# K_pfh_rerverst_rker_PSU_Rev_1_1.net
KiCad netlist of a schematic drawn in EAGLE
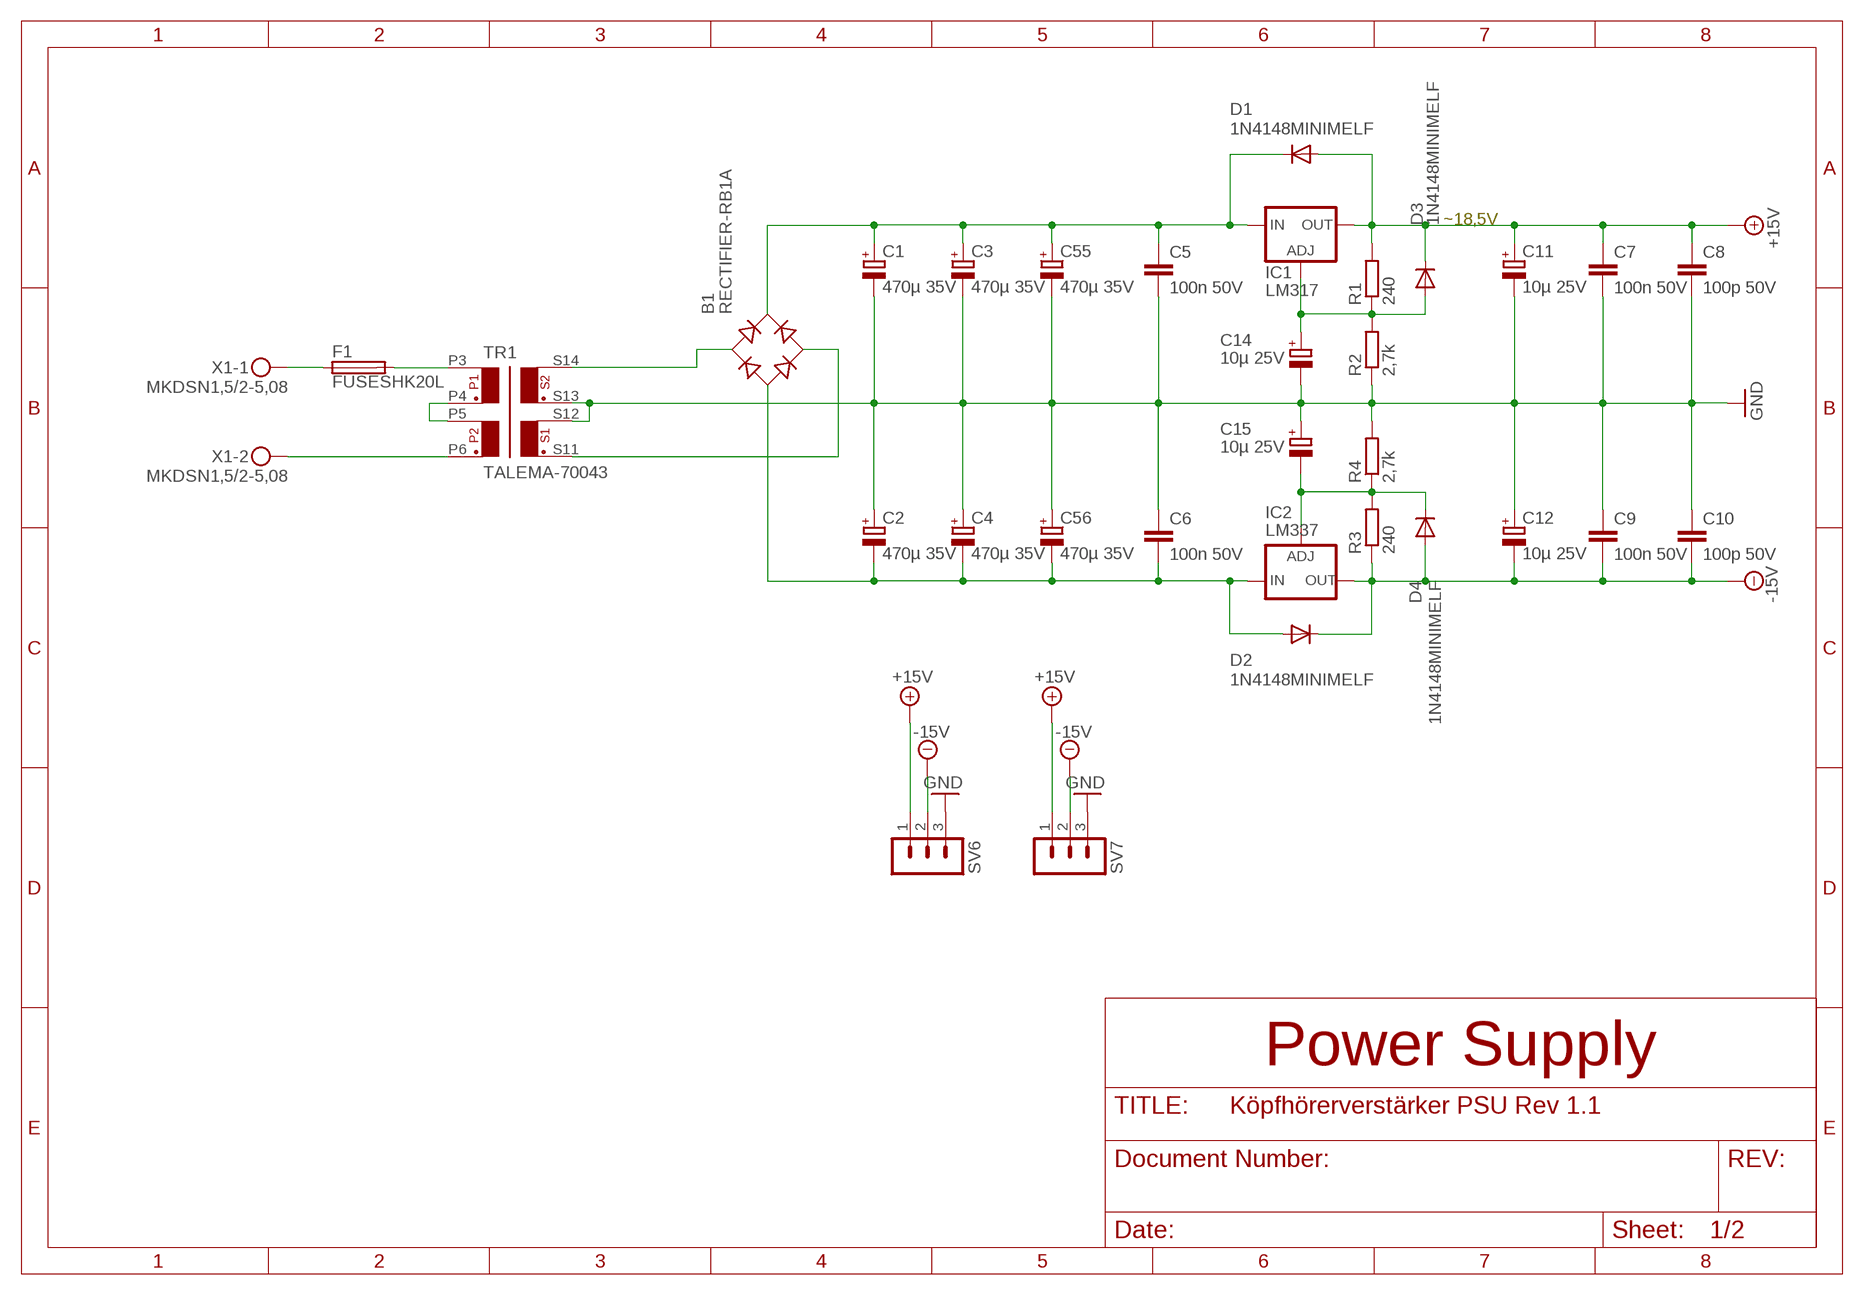
[diagram p0: schematic, sheet 1]
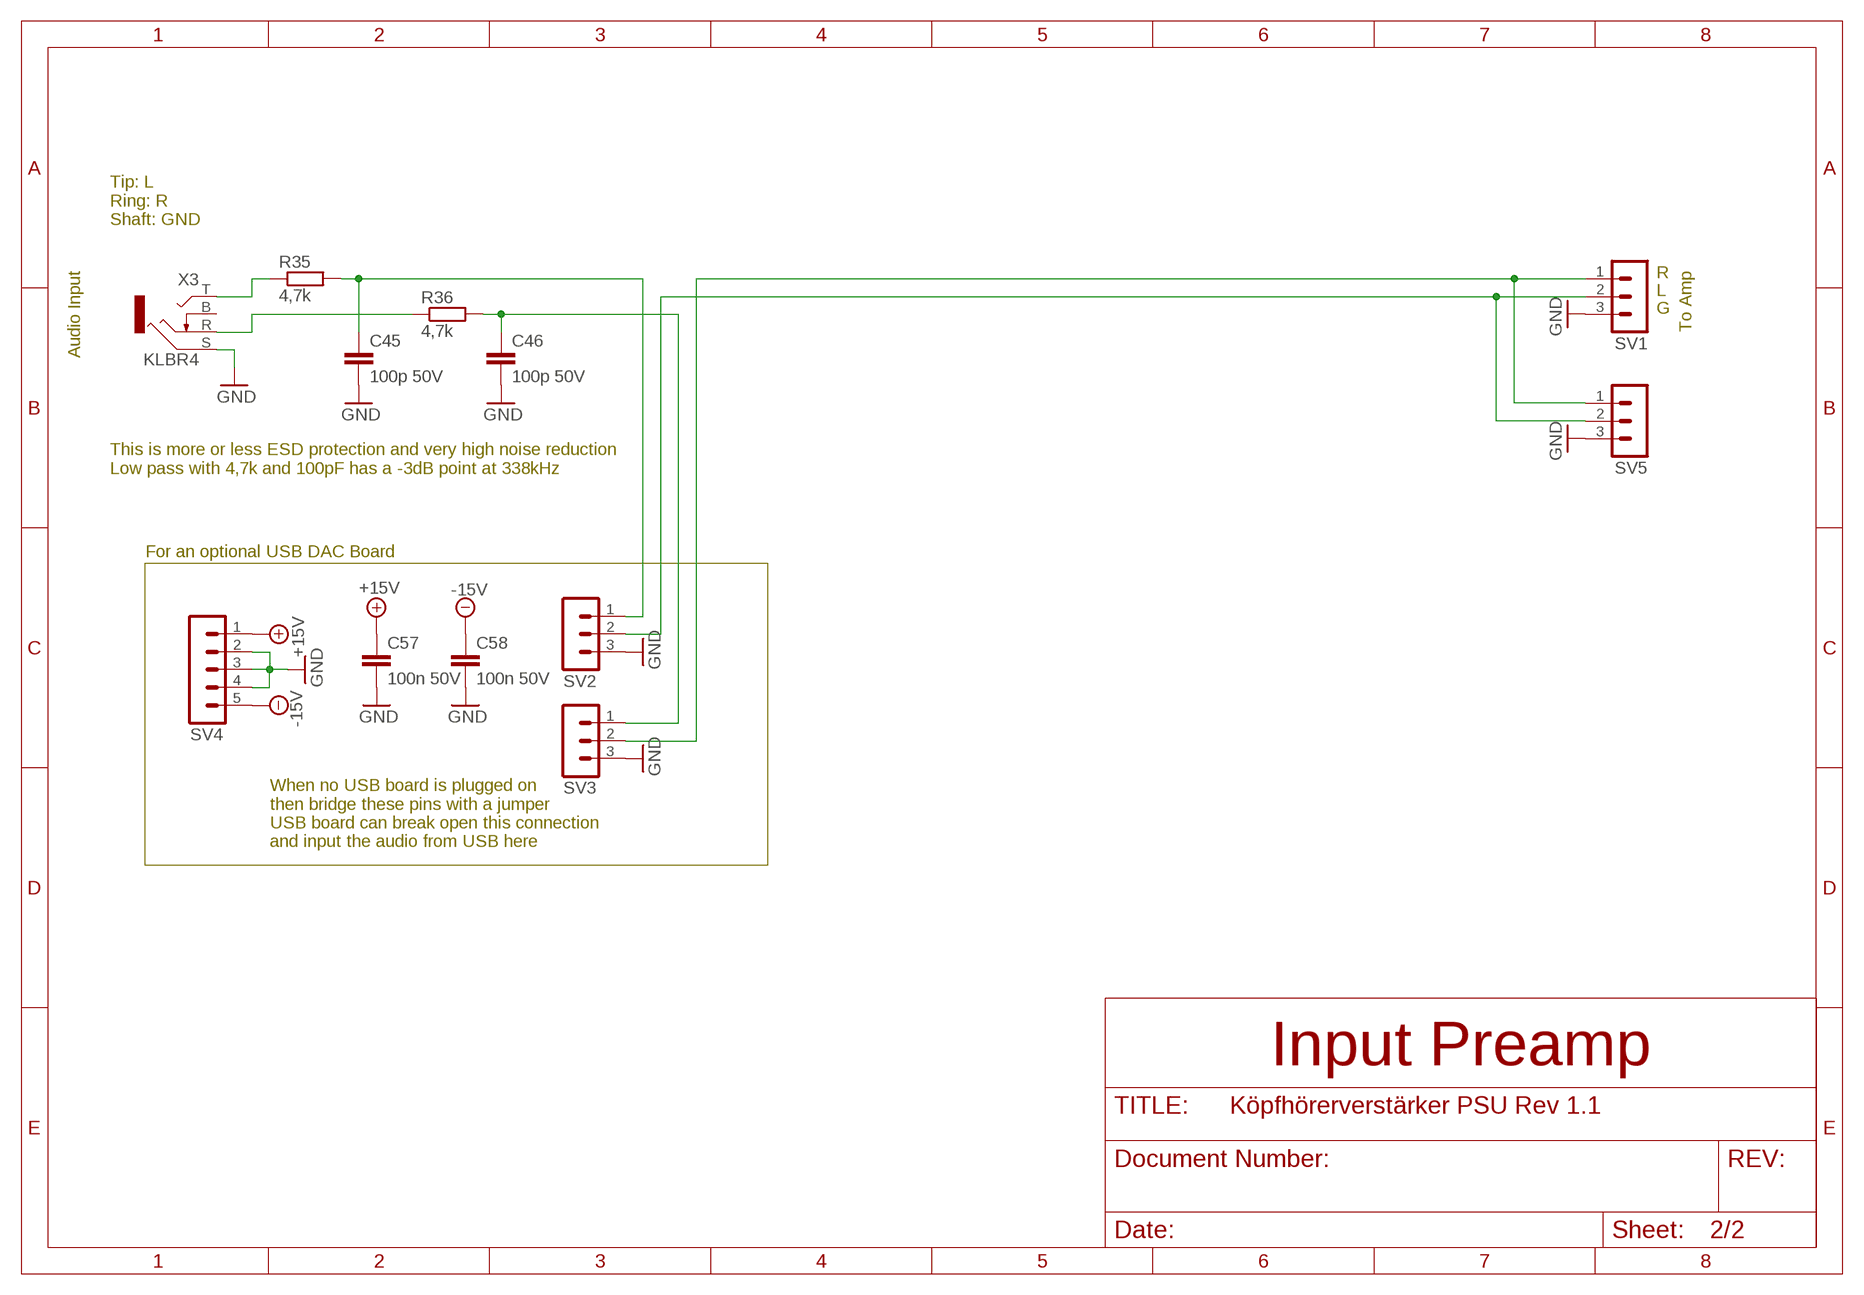
[diagram p1: schematic, sheet 2]

(export (version "E")
  (design (tool "Eeschema 10.0.6"))
  (components
    (comp (ref "B1")
      (value "RECTIFIER-RB1A")
      (footprint "eagle-import:RB1A")
      (libsource (lib "eagle-import") (part "RECTIFIER-RB1A"))
    )
    (comp (ref "C1")
      (value "470µ 35V")
      (footprint "eagle-import:E5-10,5")
      (libsource (lib "eagle-import") (part "CPOL-EUE5-10.5"))
    )
    (comp (ref "C2")
      (value "470µ 35V")
      (footprint "eagle-import:E5-10,5")
      (libsource (lib "eagle-import") (part "CPOL-EUE5-10.5"))
    )
    (comp (ref "C3")
      (value "470µ 35V")
      (footprint "eagle-import:E5-10,5")
      (libsource (lib "eagle-import") (part "CPOL-EUE5-10.5"))
    )
    (comp (ref "C4")
      (value "470µ 35V")
      (footprint "eagle-import:E5-10,5")
      (libsource (lib "eagle-import") (part "CPOL-EUE5-10.5"))
    )
    (comp (ref "C5")
      (value "100n 50V")
      (footprint "eagle-import:C0805")
      (libsource (lib "eagle-import") (part "C-EUC0805"))
    )
    (comp (ref "C6")
      (value "100n 50V")
      (footprint "eagle-import:C0805")
      (libsource (lib "eagle-import") (part "C-EUC0805"))
    )
    (comp (ref "C7")
      (value "100n 50V")
      (footprint "eagle-import:C0805")
      (libsource (lib "eagle-import") (part "C-EUC0805"))
    )
    (comp (ref "C8")
      (value "100p 50V")
      (footprint "eagle-import:C0805")
      (libsource (lib "eagle-import") (part "C-EUC0805"))
    )
    (comp (ref "C9")
      (value "100n 50V")
      (footprint "eagle-import:C0805")
      (libsource (lib "eagle-import") (part "C-EUC0805"))
    )
    (comp (ref "C10")
      (value "100p 50V")
      (footprint "eagle-import:C0805")
      (libsource (lib "eagle-import") (part "C-EUC0805"))
    )
    (comp (ref "C11")
      (value "10µ 25V")
      (footprint "eagle-import:E2,5-5")
      (libsource (lib "eagle-import") (part "CPOL-EUE2.5-5"))
    )
    (comp (ref "C12")
      (value "10µ 25V")
      (footprint "eagle-import:E2,5-5")
      (libsource (lib "eagle-import") (part "CPOL-EUE2.5-5"))
    )
    (comp (ref "C14")
      (value "10µ 25V")
      (footprint "eagle-import:E2,5-5")
      (libsource (lib "eagle-import") (part "CPOL-EUE2.5-5"))
    )
    (comp (ref "C15")
      (value "10µ 25V")
      (footprint "eagle-import:E2,5-5")
      (libsource (lib "eagle-import") (part "CPOL-EUE2.5-5"))
    )
    (comp (ref "C55")
      (value "470µ 35V")
      (footprint "eagle-import:E5-10,5")
      (libsource (lib "eagle-import") (part "CPOL-EUE5-10.5"))
    )
    (comp (ref "C56")
      (value "470µ 35V")
      (footprint "eagle-import:E5-10,5")
      (libsource (lib "eagle-import") (part "CPOL-EUE5-10.5"))
    )
    (comp (ref "D1")
      (value "1N4148MINIMELF")
      (footprint "eagle-import:MINIMELF")
      (libsource (lib "eagle-import") (part "1N4148MINIMELF"))
    )
    (comp (ref "D2")
      (value "1N4148MINIMELF")
      (footprint "eagle-import:MINIMELF")
      (libsource (lib "eagle-import") (part "1N4148MINIMELF"))
    )
    (comp (ref "D3")
      (value "1N4148MINIMELF")
      (footprint "eagle-import:MINIMELF")
      (libsource (lib "eagle-import") (part "1N4148MINIMELF"))
    )
    (comp (ref "D4")
      (value "1N4148MINIMELF")
      (footprint "eagle-import:MINIMELF")
      (libsource (lib "eagle-import") (part "1N4148MINIMELF"))
    )
    (comp (ref "F1")
      (value "FUSESHK20L")
      (footprint "eagle-import:SHK20L")
      (libsource (lib "eagle-import") (part "FUSESHK20L"))
    )
    (comp (ref "IC1")
      (value "LM317")
      (footprint "eagle-import:317TL")
      (libsource (lib "eagle-import") (part "LM317TL"))
    )
    (comp (ref "IC2")
      (value "LM337")
      (footprint "eagle-import:337TL")
      (libsource (lib "eagle-import") (part "LM337TL"))
    )
    (comp (ref "R1")
      (value "240")
      (footprint "eagle-import:R0805")
      (libsource (lib "eagle-import") (part "R-EU_R0805"))
    )
    (comp (ref "R2")
      (value "2,7k")
      (footprint "eagle-import:R0805")
      (libsource (lib "eagle-import") (part "R-EU_R0805"))
    )
    (comp (ref "R3")
      (value "240")
      (footprint "eagle-import:R0805")
      (libsource (lib "eagle-import") (part "R-EU_R0805"))
    )
    (comp (ref "R4")
      (value "2,7k")
      (footprint "eagle-import:R0805")
      (libsource (lib "eagle-import") (part "R-EU_R0805"))
    )
    (comp (ref "SV6")
      (value "MA03-1")
      (footprint "eagle-import:MA03-1")
      (libsource (lib "eagle-import") (part "MA03-1"))
    )
    (comp (ref "SV7")
      (value "MA03-1")
      (footprint "eagle-import:MA03-1")
      (libsource (lib "eagle-import") (part "MA03-1"))
    )
    (comp (ref "TR1")
      (value "TALEMA-70043")
      (footprint "eagle-import:TALEMA-70043")
      (libsource (lib "eagle-import") (part "TALEMA-70043"))
    )
    (comp (ref "X1")
      (value "MKDSN1,5/2-5,08")
      (footprint "eagle-import:MKDSN1,5_2-5,08")
      (fields (field (name "MPN") "MKDSN 1,5/2-5.08"))
      (libsource (lib "eagle-import") (part "MKDSN1,5/2-5,08"))
    )
    (comp (ref "C45")
      (value "100p 50V")
      (footprint "eagle-import:C050-025X075")
      (libsource (lib "eagle-import") (part "C-EU050-025X075"))
    )
    (comp (ref "C46")
      (value "100p 50V")
      (footprint "eagle-import:C050-025X075")
      (libsource (lib "eagle-import") (part "C-EU050-025X075"))
    )
    (comp (ref "C57")
      (value "100n 50V")
      (footprint "eagle-import:C0805")
      (libsource (lib "eagle-import") (part "C-EUC0805"))
    )
    (comp (ref "C58")
      (value "100n 50V")
      (footprint "eagle-import:C0805")
      (libsource (lib "eagle-import") (part "C-EUC0805"))
    )
    (comp (ref "R35")
      (value "4,7k")
      (footprint "eagle-import:R0805")
      (libsource (lib "eagle-import") (part "R-EU_R0805"))
    )
    (comp (ref "R36")
      (value "4,7k")
      (footprint "eagle-import:R0805")
      (libsource (lib "eagle-import") (part "R-EU_R0805"))
    )
    (comp (ref "SV1")
      (value "MA03-1")
      (footprint "eagle-import:MA03-1")
      (libsource (lib "eagle-import") (part "MA03-1"))
    )
    (comp (ref "SV2")
      (value "MA03-1")
      (footprint "eagle-import:MA03-1")
      (libsource (lib "eagle-import") (part "MA03-1"))
    )
    (comp (ref "SV3")
      (value "MA03-1")
      (footprint "eagle-import:MA03-1")
      (libsource (lib "eagle-import") (part "MA03-1"))
    )
    (comp (ref "SV4")
      (value "MA05-1")
      (footprint "eagle-import:MA05-1")
      (libsource (lib "eagle-import") (part "MA05-1"))
    )
    (comp (ref "SV5")
      (value "MA03-1")
      (footprint "eagle-import:MA03-1")
      (libsource (lib "eagle-import") (part "MA03-1"))
    )
    (comp (ref "X3")
      (value "KLBR4")
      (footprint "eagle-import:KLBR4")
      (fields (field (name "MPN") "KLBR 4"))
      (libsource (lib "eagle-import") (part "KLBR4"))
    )
  )
  (nets
    (net (code "1") (name "+15V") (class "Default")
      (node (ref "C11") (pin "+") (pinfunction "+_+") (pintype "passive"))
      (node (ref "C57") (pin "1") (pinfunction "1_1") (pintype "passive"))
      (node (ref "C7") (pin "1") (pinfunction "1_1") (pintype "passive"))
      (node (ref "C8") (pin "1") (pinfunction "1_1") (pintype "passive"))
      (node (ref "D1") (pin "A") (pinfunction "A_A") (pintype "passive"))
      (node (ref "D3") (pin "C") (pinfunction "C_C") (pintype "passive"))
      (node (ref "IC1") (pin "2") (pinfunction "OUT_2") (pintype "passive"))
      (node (ref "R1") (pin "2") (pinfunction "2_2") (pintype "passive"))
      (node (ref "SV4") (pin "1") (pinfunction "1_1") (pintype "passive"))
      (node (ref "SV6") (pin "1") (pinfunction "1_1") (pintype "passive"))
      (node (ref "SV7") (pin "1") (pinfunction "1_1") (pintype "passive"))
    )
    (net (code "2") (name "-15V") (class "Default")
      (node (ref "C10") (pin "2") (pinfunction "2_2") (pintype "passive"))
      (node (ref "C12") (pin "-") (pinfunction "-_-") (pintype "passive"))
      (node (ref "C58") (pin "1") (pinfunction "1_1") (pintype "passive"))
      (node (ref "C9") (pin "2") (pinfunction "2_2") (pintype "passive"))
      (node (ref "D2") (pin "C") (pinfunction "C_C") (pintype "passive"))
      (node (ref "D4") (pin "A") (pinfunction "A_A") (pintype "passive"))
      (node (ref "IC2") (pin "3") (pinfunction "OUT_3") (pintype "passive"))
      (node (ref "R3") (pin "1") (pinfunction "1_1") (pintype "passive"))
      (node (ref "SV4") (pin "5") (pinfunction "5_5") (pintype "passive"))
      (node (ref "SV6") (pin "2") (pinfunction "2_2") (pintype "passive"))
      (node (ref "SV7") (pin "2") (pinfunction "2_2") (pintype "passive"))
    )
    (net (code "3") (name "GND") (class "Default")
      (node (ref "C1") (pin "-") (pinfunction "-_-") (pintype "passive"))
      (node (ref "C10") (pin "1") (pinfunction "1_1") (pintype "passive"))
      (node (ref "C11") (pin "-") (pinfunction "-_-") (pintype "passive"))
      (node (ref "C12") (pin "+") (pinfunction "+_+") (pintype "passive"))
      (node (ref "C14") (pin "-") (pinfunction "-_-") (pintype "passive"))
      (node (ref "C15") (pin "+") (pinfunction "+_+") (pintype "passive"))
      (node (ref "C2") (pin "+") (pinfunction "+_+") (pintype "passive"))
      (node (ref "C3") (pin "-") (pinfunction "-_-") (pintype "passive"))
      (node (ref "C4") (pin "+") (pinfunction "+_+") (pintype "passive"))
      (node (ref "C45") (pin "2") (pinfunction "2_2") (pintype "passive"))
      (node (ref "C46") (pin "2") (pinfunction "2_2") (pintype "passive"))
      (node (ref "C5") (pin "2") (pinfunction "2_2") (pintype "passive"))
      (node (ref "C55") (pin "-") (pinfunction "-_-") (pintype "passive"))
      (node (ref "C56") (pin "+") (pinfunction "+_+") (pintype "passive"))
      (node (ref "C57") (pin "2") (pinfunction "2_2") (pintype "passive"))
      (node (ref "C58") (pin "2") (pinfunction "2_2") (pintype "passive"))
      (node (ref "C6") (pin "1") (pinfunction "1_1") (pintype "passive"))
      (node (ref "C7") (pin "2") (pinfunction "2_2") (pintype "passive"))
      (node (ref "C8") (pin "2") (pinfunction "2_2") (pintype "passive"))
      (node (ref "C9") (pin "1") (pinfunction "1_1") (pintype "passive"))
      (node (ref "R2") (pin "1") (pinfunction "1_1") (pintype "passive"))
      (node (ref "R4") (pin "2") (pinfunction "2_2") (pintype "passive"))
      (node (ref "SV1") (pin "3") (pinfunction "3_3") (pintype "passive"))
      (node (ref "SV2") (pin "3") (pinfunction "3_3") (pintype "passive"))
      (node (ref "SV3") (pin "3") (pinfunction "3_3") (pintype "passive"))
      (node (ref "SV4") (pin "2") (pinfunction "2_2") (pintype "passive"))
      (node (ref "SV4") (pin "3") (pinfunction "3_3") (pintype "passive"))
      (node (ref "SV4") (pin "4") (pinfunction "4_4") (pintype "passive"))
      (node (ref "SV5") (pin "3") (pinfunction "3_3") (pintype "passive"))
      (node (ref "SV6") (pin "3") (pinfunction "3_3") (pintype "passive"))
      (node (ref "SV7") (pin "3") (pinfunction "3_3") (pintype "passive"))
      (node (ref "TR1") (pin "S12") (pinfunction "6_S12") (pintype "passive"))
      (node (ref "TR1") (pin "S13") (pinfunction "7_S13") (pintype "passive"))
      (node (ref "X3") (pin "S") (pinfunction "S_S") (pintype "passive"))
    )
    (net (code "4") (name "Net-(C45-Pad1)") (class "Default")
      (node (ref "C45") (pin "1") (pinfunction "1_1") (pintype "passive"))
      (node (ref "R35") (pin "2") (pinfunction "2_2") (pintype "passive"))
      (node (ref "SV2") (pin "1") (pinfunction "1_1") (pintype "passive"))
    )
    (net (code "5") (name "Net-(C46-Pad1)") (class "Default")
      (node (ref "C46") (pin "1") (pinfunction "1_1") (pintype "passive"))
      (node (ref "R36") (pin "2") (pinfunction "2_2") (pintype "passive"))
      (node (ref "SV3") (pin "1") (pinfunction "1_1") (pintype "passive"))
    )
    (net (code "6") (name "Net-(F1-1)") (class "Default")
      (node (ref "F1") (pin "1A") (pinfunction "1_1A") (pintype "passive"))
      (node (ref "X1") (pin "1") (pinfunction "KL_1") (pintype "passive"))
    )
    (net (code "7") (name "Net-(F1-2)") (class "Default")
      (node (ref "F1") (pin "2A") (pinfunction "2_2A") (pintype "passive"))
      (node (ref "TR1") (pin "P3") (pinfunction "1_P3") (pintype "passive"))
    )
    (net (code "8") (name "Net-(IC1-ADJ)") (class "Default")
      (node (ref "C14") (pin "+") (pinfunction "+_+") (pintype "passive"))
      (node (ref "D3") (pin "A") (pinfunction "A_A") (pintype "passive"))
      (node (ref "IC1") (pin "1") (pinfunction "ADJ_1") (pintype "input"))
      (node (ref "R1") (pin "1") (pinfunction "1_1") (pintype "passive"))
      (node (ref "R2") (pin "2") (pinfunction "2_2") (pintype "passive"))
    )
    (net (code "9") (name "Net-(IC1-IN)") (class "Default")
      (node (ref "B1") (pin "+") (pinfunction "+_+") (pintype "passive"))
      (node (ref "C1") (pin "+") (pinfunction "+_+") (pintype "passive"))
      (node (ref "C3") (pin "+") (pinfunction "+_+") (pintype "passive"))
      (node (ref "C5") (pin "1") (pinfunction "1_1") (pintype "passive"))
      (node (ref "C55") (pin "+") (pinfunction "+_+") (pintype "passive"))
      (node (ref "D1") (pin "C") (pinfunction "C_C") (pintype "passive"))
      (node (ref "IC1") (pin "3") (pinfunction "IN_3") (pintype "input"))
    )
    (net (code "10") (name "Net-(IC2-ADJ)") (class "Default")
      (node (ref "C15") (pin "-") (pinfunction "-_-") (pintype "passive"))
      (node (ref "D4") (pin "C") (pinfunction "C_C") (pintype "passive"))
      (node (ref "IC2") (pin "1") (pinfunction "ADJ_1") (pintype "input"))
      (node (ref "R3") (pin "2") (pinfunction "2_2") (pintype "passive"))
      (node (ref "R4") (pin "1") (pinfunction "1_1") (pintype "passive"))
    )
    (net (code "11") (name "Net-(IC2-IN)") (class "Default")
      (node (ref "B1") (pin "-") (pinfunction "-_-") (pintype "passive"))
      (node (ref "C2") (pin "-") (pinfunction "-_-") (pintype "passive"))
      (node (ref "C4") (pin "-") (pinfunction "-_-") (pintype "passive"))
      (node (ref "C56") (pin "-") (pinfunction "-_-") (pintype "passive"))
      (node (ref "C6") (pin "2") (pinfunction "2_2") (pintype "passive"))
      (node (ref "D2") (pin "A") (pinfunction "A_A") (pintype "passive"))
      (node (ref "IC2") (pin "2") (pinfunction "IN_2") (pintype "input"))
    )
    (net (code "12") (name "Net-(R35-Pad1)") (class "Default")
      (node (ref "R35") (pin "1") (pinfunction "1_1") (pintype "passive"))
      (node (ref "X3") (pin "T") (pinfunction "T_T") (pintype "passive"))
    )
    (net (code "13") (name "Net-(R36-Pad1)") (class "Default")
      (node (ref "R36") (pin "1") (pinfunction "1_1") (pintype "passive"))
      (node (ref "X3") (pin "R") (pinfunction "R_R") (pintype "passive"))
    )
    (net (code "14") (name "Net-(SV1-Pad1)") (class "Default")
      (node (ref "SV1") (pin "1") (pinfunction "1_1") (pintype "passive"))
      (node (ref "SV3") (pin "2") (pinfunction "2_2") (pintype "passive"))
      (node (ref "SV5") (pin "1") (pinfunction "1_1") (pintype "passive"))
    )
    (net (code "15") (name "Net-(SV1-Pad2)") (class "Default")
      (node (ref "SV1") (pin "2") (pinfunction "2_2") (pintype "passive"))
      (node (ref "SV2") (pin "2") (pinfunction "2_2") (pintype "passive"))
      (node (ref "SV5") (pin "2") (pinfunction "2_2") (pintype "passive"))
    )
    (net (code "16") (name "Net-(TR1-2)") (class "Default")
      (node (ref "TR1") (pin "P4") (pinfunction "2_P4") (pintype "passive"))
      (node (ref "TR1") (pin "P5") (pinfunction "3_P5") (pintype "passive"))
    )
    (net (code "17") (name "Net-(TR1-4)") (class "Default")
      (node (ref "TR1") (pin "P6") (pinfunction "4_P6") (pintype "passive"))
      (node (ref "X1") (pin "2") (pinfunction "KL_2") (pintype "passive"))
    )
    (net (code "18") (name "Net-(TR1-5)") (class "Default")
      (node (ref "B1") (pin "AC2") (pinfunction "AC2_AC2") (pintype "passive"))
      (node (ref "TR1") (pin "S11") (pinfunction "5_S11") (pintype "passive"))
    )
    (net (code "19") (name "Net-(TR1-8)") (class "Default")
      (node (ref "B1") (pin "AC1") (pinfunction "AC1_AC1") (pintype "passive"))
      (node (ref "TR1") (pin "S14") (pinfunction "8_S14") (pintype "passive"))
    )
    (net (code "20") (name "unconnected-(X3-PadB)") (class "Default")
      (node (ref "X3") (pin "B") (pinfunction "B_B") (pintype "passive"))
    )
  )
)
